# stm32_vcc.net
KiCad netlist of a schematic drawn in Altium Designer
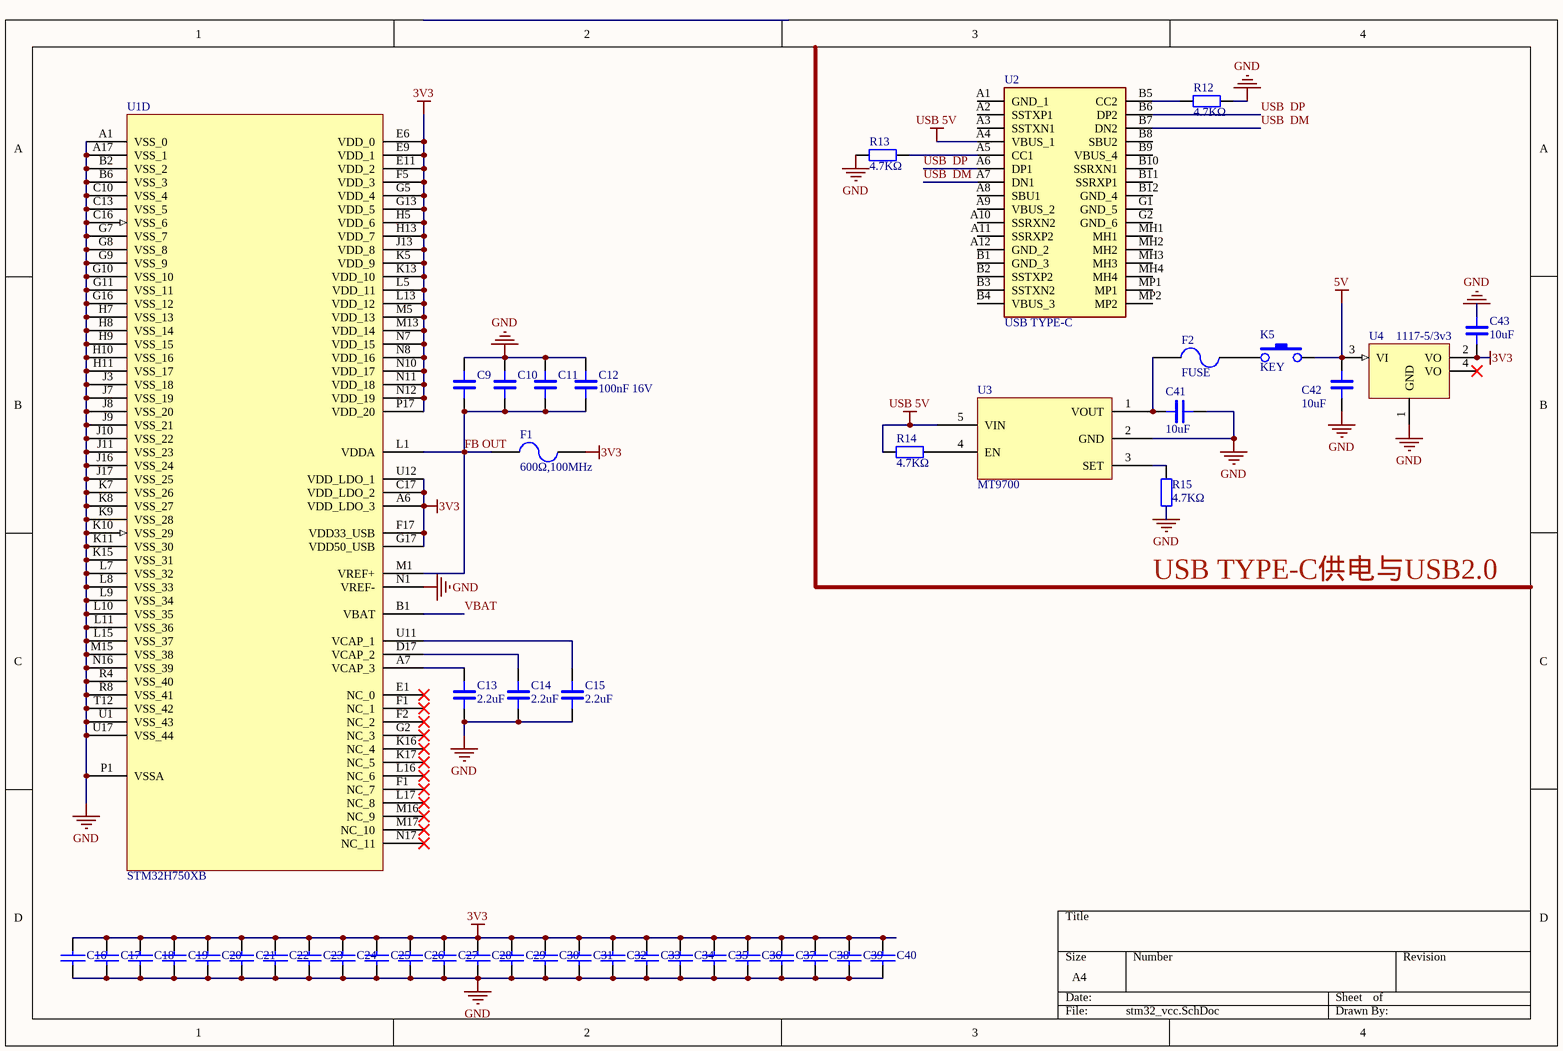
[diagram p0: stm32_vcc.SchDoc]

(export (version "E")
  (design (tool "Eeschema 10.0.6"))
  (components
    (comp (ref "C9")
      (value "100nF 16V")
      (footprint "0805")
      (description "Capacitor")
      (libsource (lib "General") (part "CAP"))
    )
    (comp (ref "C10")
      (value "100nF 16V")
      (footprint "0805")
      (description "Capacitor")
      (libsource (lib "General") (part "CAP"))
    )
    (comp (ref "C11")
      (value "100nF 16V")
      (footprint "0805")
      (description "Capacitor")
      (libsource (lib "General") (part "CAP"))
    )
    (comp (ref "C12")
      (value "100nF 16V")
      (footprint "0805")
      (description "Capacitor")
      (libsource (lib "General") (part "CAP"))
    )
    (comp (ref "C13")
      (value "2.2uF")
      (footprint "0805")
      (description "Capacitor")
      (libsource (lib "General") (part "CAP"))
    )
    (comp (ref "C14")
      (value "2.2uF")
      (footprint "0805")
      (description "Capacitor")
      (libsource (lib "General") (part "CAP"))
    )
    (comp (ref "C15")
      (value "2.2uF")
      (footprint "0805")
      (description "Capacitor")
      (libsource (lib "General") (part "CAP"))
    )
    (comp (ref "C16")
      (value "104 16V")
      (footprint "0805C")
      (description "无极性电容")
      (libsource (lib "电容") (part "CAP"))
    )
    (comp (ref "C17")
      (value "104 16V")
      (footprint "0805C")
      (description "无极性电容")
      (libsource (lib "电容") (part "CAP"))
    )
    (comp (ref "C18")
      (value "104 16V")
      (footprint "0805C")
      (description "无极性电容")
      (libsource (lib "电容") (part "CAP"))
    )
    (comp (ref "C19")
      (value "104 16V")
      (footprint "0805C")
      (description "无极性电容")
      (libsource (lib "电容") (part "CAP"))
    )
    (comp (ref "C20")
      (value "104 16V")
      (footprint "0805C")
      (description "无极性电容")
      (libsource (lib "电容") (part "CAP"))
    )
    (comp (ref "C21")
      (value "104 16V")
      (footprint "0805C")
      (description "无极性电容")
      (libsource (lib "电容") (part "CAP"))
    )
    (comp (ref "C22")
      (value "104 16V")
      (footprint "0805C")
      (description "无极性电容")
      (libsource (lib "电容") (part "CAP"))
    )
    (comp (ref "C23")
      (value "104 16V")
      (footprint "0805C")
      (description "无极性电容")
      (libsource (lib "电容") (part "CAP"))
    )
    (comp (ref "C24")
      (value "104 16V")
      (footprint "0805C")
      (description "无极性电容")
      (libsource (lib "电容") (part "CAP"))
    )
    (comp (ref "C25")
      (value "104 16V")
      (footprint "0805C")
      (description "无极性电容")
      (libsource (lib "电容") (part "CAP"))
    )
    (comp (ref "C26")
      (value "104 16V")
      (footprint "0805C")
      (description "无极性电容")
      (libsource (lib "电容") (part "CAP"))
    )
    (comp (ref "C27")
      (value "104 16V")
      (footprint "0805C")
      (description "无极性电容")
      (libsource (lib "电容") (part "CAP"))
    )
    (comp (ref "C28")
      (value "104 16V")
      (footprint "0805C")
      (description "无极性电容")
      (libsource (lib "电容") (part "CAP"))
    )
    (comp (ref "C29")
      (value "104 16V")
      (footprint "0805C")
      (description "无极性电容")
      (libsource (lib "电容") (part "CAP"))
    )
    (comp (ref "C30")
      (value "104 16V")
      (footprint "0805C")
      (description "无极性电容")
      (libsource (lib "电容") (part "CAP"))
    )
    (comp (ref "C31")
      (value "104 16V")
      (footprint "0805C")
      (description "无极性电容")
      (libsource (lib "电容") (part "CAP"))
    )
    (comp (ref "C32")
      (value "104 16V")
      (footprint "0805C")
      (description "无极性电容")
      (libsource (lib "电容") (part "CAP"))
    )
    (comp (ref "C33")
      (value "104 16V")
      (footprint "0805C")
      (description "无极性电容")
      (libsource (lib "电容") (part "CAP"))
    )
    (comp (ref "C34")
      (value "104 16V")
      (footprint "0805C")
      (description "无极性电容")
      (libsource (lib "电容") (part "CAP"))
    )
    (comp (ref "C35")
      (value "104 16V")
      (footprint "0805C")
      (description "无极性电容")
      (libsource (lib "电容") (part "CAP"))
    )
    (comp (ref "C36")
      (value "104 16V")
      (footprint "0805C")
      (description "无极性电容")
      (libsource (lib "电容") (part "CAP"))
    )
    (comp (ref "C37")
      (value "104 16V")
      (footprint "0805C")
      (description "无极性电容")
      (libsource (lib "电容") (part "CAP"))
    )
    (comp (ref "C38")
      (value "104 16V")
      (footprint "0805C")
      (description "无极性电容")
      (libsource (lib "电容") (part "CAP"))
    )
    (comp (ref "C39")
      (value "104 16V")
      (footprint "0805C")
      (description "无极性电容")
      (libsource (lib "电容") (part "CAP"))
    )
    (comp (ref "C40")
      (value "104 16V")
      (footprint "0805C")
      (description "无极性电容")
      (libsource (lib "电容") (part "CAP"))
    )
    (comp (ref "C41")
      (value "10uF")
      (footprint "0805")
      (description "Capacitor")
      (libsource (lib "General") (part "CAP"))
    )
    (comp (ref "C42")
      (value "10uF")
      (footprint "0805")
      (description "Capacitor")
      (libsource (lib "General") (part "CAP"))
    )
    (comp (ref "C43")
      (value "10uF")
      (footprint "CAP-0805")
      (description "Capacitor")
      (libsource (lib "General") (part "CAP"))
    )
    (comp (ref "F1") (value "600Ω,100MHz") (footprint "FUSE-1210") (libsource (lib "保险丝") (part "FUSE")))
    (comp (ref "F2")
      (value "FUSE")
      (footprint "FUSE-1210")
      (description "1000mA")
      (libsource (lib "保险丝") (part "FUSE"))
    )
    (comp (ref "K5") (value "KEY") (footprint "DIP-3X6X4.3") (libsource (lib "轻触开关") (part "KEY")))
    (comp (ref "R12")
      (value "4.7KΩ")
      (footprint "0805")
      (description "Resistor")
      (libsource (lib "General") (part "RES"))
    )
    (comp (ref "R13")
      (value "4.7KΩ")
      (footprint "0805")
      (description "Resistor")
      (libsource (lib "General") (part "RES"))
    )
    (comp (ref "R14")
      (value "4.7KΩ")
      (footprint "0805")
      (description "Resistor")
      (libsource (lib "General") (part "RES"))
    )
    (comp (ref "R15")
      (value "4.7KΩ")
      (footprint "0805")
      (description "Resistor")
      (libsource (lib "") (part "RES_1"))
    )
    (comp (ref "U1")
      (value "STM32H750XB")
      (footprint "BGA265C80P17X17_1400X1400X110")
      (libsource (lib "MainBoard") (part "STM32H750XB"))
    )
    (comp (ref "U2")
      (value "USB TYPE-C")
      (footprint "SamacSys:632723100011")
      (description "Integrated Circuit")
      (fields
        (field (name "MANUFACTURER_PART_NUMBER") "632723100011")
        (field (name "MOUSER PART NUMBER") "710-632723100011")
      )
      (libsource (lib "*") (part "632723100011"))
    )
    (comp (ref "U3") (value "MT9700") (footprint "SOT-23-5") (libsource (lib "MainBoard") (part "MT9700")))
    (comp (ref "U4")
      (value "1117-5/3v3")
      (footprint "SOT-23")
      (description "Linear Regulator")
      (libsource (lib "General") (part "1117"))
    )
  )
  (nets
    (net (code "1") (name "/FB OUT") (class "Default")
      (node (ref "C10") (pin "1") (pinfunction "1_1") (pintype "passive"))
      (node (ref "C11") (pin "1") (pinfunction "1_1") (pintype "passive"))
      (node (ref "C12") (pin "1") (pinfunction "1_1") (pintype "passive"))
      (node (ref "C9") (pin "1") (pinfunction "1_1") (pintype "passive"))
      (node (ref "F1") (pin "1") (pinfunction "1_1") (pintype "passive"))
      (node (ref "U1") (pin "L1") (pinfunction "VDDA_L1") (pintype "passive"))
      (node (ref "U1") (pin "M1") (pinfunction "VREF+_M1") (pintype "passive"))
    )
    (net (code "2") (name "/USB  DM") (class "Default")
      (node (ref "U2") (pin "A7") (pinfunction "DN1_A7") (pintype "passive"))
      (node (ref "U2") (pin "B7") (pinfunction "DN2_B7") (pintype "passive"))
    )
    (net (code "3") (name "/USB  DP") (class "Default")
      (node (ref "U2") (pin "A6") (pinfunction "DP1_A6") (pintype "passive"))
      (node (ref "U2") (pin "B6") (pinfunction "DP2_B6") (pintype "passive"))
    )
    (net (code "4") (name "/VBAT") (class "Default")
      (node (ref "U1") (pin "B1") (pinfunction "VBAT_B1") (pintype "passive"))
    )
    (net (code "5") (name "3V3") (class "Default")
      (node (ref "C16") (pin "2") (pinfunction "2_2") (pintype "passive"))
      (node (ref "C17") (pin "2") (pinfunction "2_2") (pintype "passive"))
      (node (ref "C18") (pin "2") (pinfunction "2_2") (pintype "passive"))
      (node (ref "C19") (pin "2") (pinfunction "2_2") (pintype "passive"))
      (node (ref "C20") (pin "2") (pinfunction "2_2") (pintype "passive"))
      (node (ref "C21") (pin "2") (pinfunction "2_2") (pintype "passive"))
      (node (ref "C22") (pin "2") (pinfunction "2_2") (pintype "passive"))
      (node (ref "C23") (pin "2") (pinfunction "2_2") (pintype "passive"))
      (node (ref "C24") (pin "2") (pinfunction "2_2") (pintype "passive"))
      (node (ref "C25") (pin "2") (pinfunction "2_2") (pintype "passive"))
      (node (ref "C26") (pin "2") (pinfunction "2_2") (pintype "passive"))
      (node (ref "C27") (pin "2") (pinfunction "2_2") (pintype "passive"))
      (node (ref "C28") (pin "2") (pinfunction "2_2") (pintype "passive"))
      (node (ref "C29") (pin "2") (pinfunction "2_2") (pintype "passive"))
      (node (ref "C30") (pin "2") (pinfunction "2_2") (pintype "passive"))
      (node (ref "C31") (pin "2") (pinfunction "2_2") (pintype "passive"))
      (node (ref "C32") (pin "2") (pinfunction "2_2") (pintype "passive"))
      (node (ref "C33") (pin "2") (pinfunction "2_2") (pintype "passive"))
      (node (ref "C34") (pin "2") (pinfunction "2_2") (pintype "passive"))
      (node (ref "C35") (pin "2") (pinfunction "2_2") (pintype "passive"))
      (node (ref "C36") (pin "2") (pinfunction "2_2") (pintype "passive"))
      (node (ref "C37") (pin "2") (pinfunction "2_2") (pintype "passive"))
      (node (ref "C38") (pin "2") (pinfunction "2_2") (pintype "passive"))
      (node (ref "C39") (pin "2") (pinfunction "2_2") (pintype "passive"))
      (node (ref "C40") (pin "2") (pinfunction "2_2") (pintype "passive"))
      (node (ref "C43") (pin "2") (pinfunction "2_2") (pintype "passive"))
      (node (ref "F1") (pin "2") (pinfunction "2_2") (pintype "passive"))
      (node (ref "U1") (pin "A6") (pinfunction "VDD_LDO_3_A6") (pintype "passive"))
      (node (ref "U1") (pin "C17") (pinfunction "VDD_LDO_2_C17") (pintype "passive"))
      (node (ref "U1") (pin "E11") (pinfunction "VDD_2_E11") (pintype "passive"))
      (node (ref "U1") (pin "E6") (pinfunction "VDD_0_E6") (pintype "passive"))
      (node (ref "U1") (pin "E9") (pinfunction "VDD_1_E9") (pintype "passive"))
      (node (ref "U1") (pin "F17") (pinfunction "VDD33_USB_F17") (pintype "passive"))
      (node (ref "U1") (pin "F5") (pinfunction "VDD_3_F5") (pintype "passive"))
      (node (ref "U1") (pin "G13") (pinfunction "VDD_5_G13") (pintype "passive"))
      (node (ref "U1") (pin "G17") (pinfunction "VDD50_USB_G17") (pintype "passive"))
      (node (ref "U1") (pin "G5") (pinfunction "VDD_4_G5") (pintype "passive"))
      (node (ref "U1") (pin "H13") (pinfunction "VDD_7_H13") (pintype "passive"))
      (node (ref "U1") (pin "H5") (pinfunction "VDD_6_H5") (pintype "passive"))
      (node (ref "U1") (pin "J13") (pinfunction "VDD_8_J13") (pintype "passive"))
      (node (ref "U1") (pin "K13") (pinfunction "VDD_10_K13") (pintype "passive"))
      (node (ref "U1") (pin "K5") (pinfunction "VDD_9_K5") (pintype "passive"))
      (node (ref "U1") (pin "L13") (pinfunction "VDD_12_L13") (pintype "passive"))
      (node (ref "U1") (pin "L5") (pinfunction "VDD_11_L5") (pintype "passive"))
      (node (ref "U1") (pin "M13") (pinfunction "VDD_14_M13") (pintype "passive"))
      (node (ref "U1") (pin "M5") (pinfunction "VDD_13_M5") (pintype "passive"))
      (node (ref "U1") (pin "N10") (pinfunction "VDD_17_N10") (pintype "passive"))
      (node (ref "U1") (pin "N11") (pinfunction "VDD_18_N11") (pintype "passive"))
      (node (ref "U1") (pin "N12") (pinfunction "VDD_19_N12") (pintype "passive"))
      (node (ref "U1") (pin "N7") (pinfunction "VDD_15_N7") (pintype "passive"))
      (node (ref "U1") (pin "N8") (pinfunction "VDD_16_N8") (pintype "passive"))
      (node (ref "U1") (pin "P17") (pinfunction "VDD_20_P17") (pintype "passive"))
      (node (ref "U1") (pin "U12") (pinfunction "VDD_LDO_1_U12") (pintype "passive"))
      (node (ref "U4") (pin "2") (pinfunction "VO_2") (pintype "power_in"))
    )
    (net (code "6") (name "5V") (class "Default")
      (node (ref "C42") (pin "1") (pinfunction "1_1") (pintype "passive"))
      (node (ref "K5") (pin "3") (pinfunction "3_3") (pintype "passive"))
      (node (ref "U4") (pin "3") (pinfunction "VI_3") (pintype "input"))
    )
    (net (code "7") (name "GND") (class "Default")
      (node (ref "C10") (pin "2") (pinfunction "2_2") (pintype "passive"))
      (node (ref "C11") (pin "2") (pinfunction "2_2") (pintype "passive"))
      (node (ref "C12") (pin "2") (pinfunction "2_2") (pintype "passive"))
      (node (ref "C13") (pin "1") (pinfunction "1_1") (pintype "passive"))
      (node (ref "C14") (pin "1") (pinfunction "1_1") (pintype "passive"))
      (node (ref "C15") (pin "1") (pinfunction "1_1") (pintype "passive"))
      (node (ref "C16") (pin "1") (pinfunction "1_1") (pintype "passive"))
      (node (ref "C17") (pin "1") (pinfunction "1_1") (pintype "passive"))
      (node (ref "C18") (pin "1") (pinfunction "1_1") (pintype "passive"))
      (node (ref "C19") (pin "1") (pinfunction "1_1") (pintype "passive"))
      (node (ref "C20") (pin "1") (pinfunction "1_1") (pintype "passive"))
      (node (ref "C21") (pin "1") (pinfunction "1_1") (pintype "passive"))
      (node (ref "C22") (pin "1") (pinfunction "1_1") (pintype "passive"))
      (node (ref "C23") (pin "1") (pinfunction "1_1") (pintype "passive"))
      (node (ref "C24") (pin "1") (pinfunction "1_1") (pintype "passive"))
      (node (ref "C25") (pin "1") (pinfunction "1_1") (pintype "passive"))
      (node (ref "C26") (pin "1") (pinfunction "1_1") (pintype "passive"))
      (node (ref "C27") (pin "1") (pinfunction "1_1") (pintype "passive"))
      (node (ref "C28") (pin "1") (pinfunction "1_1") (pintype "passive"))
      (node (ref "C29") (pin "1") (pinfunction "1_1") (pintype "passive"))
      (node (ref "C30") (pin "1") (pinfunction "1_1") (pintype "passive"))
      (node (ref "C31") (pin "1") (pinfunction "1_1") (pintype "passive"))
      (node (ref "C32") (pin "1") (pinfunction "1_1") (pintype "passive"))
      (node (ref "C33") (pin "1") (pinfunction "1_1") (pintype "passive"))
      (node (ref "C34") (pin "1") (pinfunction "1_1") (pintype "passive"))
      (node (ref "C35") (pin "1") (pinfunction "1_1") (pintype "passive"))
      (node (ref "C36") (pin "1") (pinfunction "1_1") (pintype "passive"))
      (node (ref "C37") (pin "1") (pinfunction "1_1") (pintype "passive"))
      (node (ref "C38") (pin "1") (pinfunction "1_1") (pintype "passive"))
      (node (ref "C39") (pin "1") (pinfunction "1_1") (pintype "passive"))
      (node (ref "C40") (pin "1") (pinfunction "1_1") (pintype "passive"))
      (node (ref "C41") (pin "1") (pinfunction "1_1") (pintype "passive"))
      (node (ref "C42") (pin "2") (pinfunction "2_2") (pintype "passive"))
      (node (ref "C43") (pin "1") (pinfunction "1_1") (pintype "passive"))
      (node (ref "C9") (pin "2") (pinfunction "2_2") (pintype "passive"))
      (node (ref "R12") (pin "1") (pinfunction "1_1") (pintype "passive"))
      (node (ref "R13") (pin "2") (pinfunction "2_2") (pintype "passive"))
      (node (ref "R15") (pin "2") (pinfunction "2_2") (pintype "passive"))
      (node (ref "U1") (pin "A1") (pinfunction "VSS_0_A1") (pintype "passive"))
      (node (ref "U1") (pin "A17") (pinfunction "VSS_1_A17") (pintype "passive"))
      (node (ref "U1") (pin "B2") (pinfunction "VSS_2_B2") (pintype "passive"))
      (node (ref "U1") (pin "B6") (pinfunction "VSS_3_B6") (pintype "passive"))
      (node (ref "U1") (pin "C10") (pinfunction "VSS_4_C10") (pintype "passive"))
      (node (ref "U1") (pin "C13") (pinfunction "VSS_5_C13") (pintype "passive"))
      (node (ref "U1") (pin "C16") (pinfunction "VSS_6_C16") (pintype "input"))
      (node (ref "U1") (pin "G10") (pinfunction "VSS_10_G10") (pintype "passive"))
      (node (ref "U1") (pin "G11") (pinfunction "VSS_11_G11") (pintype "passive"))
      (node (ref "U1") (pin "G16") (pinfunction "VSS_12_G16") (pintype "passive"))
      (node (ref "U1") (pin "G7") (pinfunction "VSS_7_G7") (pintype "passive"))
      (node (ref "U1") (pin "G8") (pinfunction "VSS_8_G8") (pintype "passive"))
      (node (ref "U1") (pin "G9") (pinfunction "VSS_9_G9") (pintype "passive"))
      (node (ref "U1") (pin "H10") (pinfunction "VSS_16_H10") (pintype "passive"))
      (node (ref "U1") (pin "H11") (pinfunction "VSS_17_H11") (pintype "passive"))
      (node (ref "U1") (pin "H7") (pinfunction "VSS_13_H7") (pintype "passive"))
      (node (ref "U1") (pin "H8") (pinfunction "VSS_14_H8") (pintype "passive"))
      (node (ref "U1") (pin "H9") (pinfunction "VSS_15_H9") (pintype "passive"))
      (node (ref "U1") (pin "J10") (pinfunction "VSS_22_J10") (pintype "passive"))
      (node (ref "U1") (pin "J11") (pinfunction "VSS_23_J11") (pintype "passive"))
      (node (ref "U1") (pin "J16") (pinfunction "VSS_24_J16") (pintype "power_in"))
      (node (ref "U1") (pin "J17") (pinfunction "VSS_25_J17") (pintype "passive"))
      (node (ref "U1") (pin "J3") (pinfunction "VSS_18_J3") (pintype "passive"))
      (node (ref "U1") (pin "J7") (pinfunction "VSS_19_J7") (pintype "passive"))
      (node (ref "U1") (pin "J8") (pinfunction "VSS_20_J8") (pintype "passive"))
      (node (ref "U1") (pin "J9") (pinfunction "VSS_21_J9") (pintype "passive"))
      (node (ref "U1") (pin "K10") (pinfunction "VSS_29_K10") (pintype "input"))
      (node (ref "U1") (pin "K11") (pinfunction "VSS_30_K11") (pintype "passive"))
      (node (ref "U1") (pin "K15") (pinfunction "VSS_31_K15") (pintype "passive"))
      (node (ref "U1") (pin "K7") (pinfunction "VSS_26_K7") (pintype "passive"))
      (node (ref "U1") (pin "K8") (pinfunction "VSS_27_K8") (pintype "passive"))
      (node (ref "U1") (pin "K9") (pinfunction "VSS_28_K9") (pintype "passive"))
      (node (ref "U1") (pin "L10") (pinfunction "VSS_35_L10") (pintype "passive"))
      (node (ref "U1") (pin "L11") (pinfunction "VSS_36_L11") (pintype "passive"))
      (node (ref "U1") (pin "L15") (pinfunction "VSS_37_L15") (pintype "passive"))
      (node (ref "U1") (pin "L7") (pinfunction "VSS_32_L7") (pintype "passive"))
      (node (ref "U1") (pin "L8") (pinfunction "VSS_33_L8") (pintype "passive"))
      (node (ref "U1") (pin "L9") (pinfunction "VSS_34_L9") (pintype "passive"))
      (node (ref "U1") (pin "M15") (pinfunction "VSS_38_M15") (pintype "passive"))
      (node (ref "U1") (pin "N1") (pinfunction "VREF-_N1") (pintype "passive"))
      (node (ref "U1") (pin "N16") (pinfunction "VSS_39_N16") (pintype "passive"))
      (node (ref "U1") (pin "P1") (pinfunction "VSSA_P1") (pintype "passive"))
      (node (ref "U1") (pin "R4") (pinfunction "VSS_40_R4") (pintype "passive"))
      (node (ref "U1") (pin "R8") (pinfunction "VSS_41_R8") (pintype "passive"))
      (node (ref "U1") (pin "T12") (pinfunction "VSS_42_T12") (pintype "passive"))
      (node (ref "U1") (pin "U1") (pinfunction "VSS_43_U1") (pintype "passive"))
      (node (ref "U1") (pin "U17") (pinfunction "VSS_44_U17") (pintype "passive"))
      (node (ref "U3") (pin "2") (pinfunction "GND_2") (pintype "passive"))
      (node (ref "U4") (pin "1") (pinfunction "GND_1") (pintype "power_in"))
    )
    (net (code "8") (name "Net-(F2-Pad2)") (class "Default")
      (node (ref "F2") (pin "2") (pinfunction "2_2") (pintype "passive"))
      (node (ref "K5") (pin "1") (pinfunction "1_1") (pintype "passive"))
    )
    (net (code "9") (name "Net-(U1D-VCAP_1)") (class "Default")
      (node (ref "C15") (pin "2") (pinfunction "2_2") (pintype "passive"))
      (node (ref "U1") (pin "U11") (pinfunction "VCAP_1_U11") (pintype "passive"))
    )
    (net (code "10") (name "Net-(U1D-VCAP_2)") (class "Default")
      (node (ref "C14") (pin "2") (pinfunction "2_2") (pintype "passive"))
      (node (ref "U1") (pin "D17") (pinfunction "VCAP_2_D17") (pintype "passive"))
    )
    (net (code "11") (name "Net-(U1D-VCAP_3)") (class "Default")
      (node (ref "C13") (pin "2") (pinfunction "2_2") (pintype "passive"))
      (node (ref "U1") (pin "A7") (pinfunction "VCAP_3_A7") (pintype "passive"))
    )
    (net (code "12") (name "Net-(U2-CC1)") (class "Default")
      (node (ref "R13") (pin "1") (pinfunction "1_1") (pintype "passive"))
      (node (ref "U2") (pin "A5") (pinfunction "CC1_A5") (pintype "passive"))
    )
    (net (code "13") (name "Net-(U2-CC2)") (class "Default")
      (node (ref "R12") (pin "2") (pinfunction "2_2") (pintype "passive"))
      (node (ref "U2") (pin "B5") (pinfunction "CC2_B5") (pintype "passive"))
    )
    (net (code "14") (name "Net-(U3-EN)") (class "Default")
      (node (ref "R14") (pin "1") (pinfunction "1_1") (pintype "passive"))
      (node (ref "U3") (pin "4") (pinfunction "EN_4") (pintype "passive"))
    )
    (net (code "15") (name "Net-(U3-SET)") (class "Default")
      (node (ref "R15") (pin "1") (pinfunction "1_1") (pintype "passive"))
      (node (ref "U3") (pin "3") (pinfunction "SET_3") (pintype "passive"))
    )
    (net (code "16") (name "Net-(U3-VOUT)") (class "Default")
      (node (ref "C41") (pin "2") (pinfunction "2_2") (pintype "passive"))
      (node (ref "F2") (pin "1") (pinfunction "1_1") (pintype "passive"))
      (node (ref "U3") (pin "1") (pinfunction "VOUT_1") (pintype "passive"))
    )
    (net (code "17") (name "USB 5V") (class "Default")
      (node (ref "R14") (pin "2") (pinfunction "2_2") (pintype "passive"))
      (node (ref "U2") (pin "A4") (pinfunction "VBUS_1_A4") (pintype "passive"))
      (node (ref "U3") (pin "5") (pinfunction "VIN_5") (pintype "passive"))
    )
    (net (code "18") (name "unconnected-(U1D-NC_0-PadE1)") (class "Default")
      (node (ref "U1") (pin "E1") (pinfunction "NC_0_E1") (pintype "passive+no_connect"))
    )
    (net (code "19") (name "unconnected-(U1D-NC_1-PadF1)") (class "Default")
      (node (ref "U1") (pin "F1") (pinfunction "NC_1_F1") (pintype "passive+no_connect"))
    )
    (net (code "20") (name "unconnected-(U1D-NC_2-PadF2)") (class "Default")
      (node (ref "U1") (pin "F2") (pinfunction "NC_2_F2") (pintype "passive+no_connect"))
    )
    (net (code "21") (name "unconnected-(U1D-NC_3-PadG2)") (class "Default")
      (node (ref "U1") (pin "G2") (pinfunction "NC_3_G2") (pintype "passive+no_connect"))
    )
    (net (code "22") (name "unconnected-(U1D-NC_4-PadK16)") (class "Default")
      (node (ref "U1") (pin "K16") (pinfunction "NC_4_K16") (pintype "passive+no_connect"))
    )
    (net (code "23") (name "unconnected-(U1D-NC_5-PadK17)") (class "Default")
      (node (ref "U1") (pin "K17") (pinfunction "NC_5_K17") (pintype "passive+no_connect"))
    )
    (net (code "24") (name "unconnected-(U1D-NC_6-PadL16)") (class "Default")
      (node (ref "U1") (pin "L16") (pinfunction "NC_6_L16") (pintype "passive+no_connect"))
    )
    (net (code "25") (name "unconnected-(U1D-NC_7-PadF1)") (class "Default")
      (node (ref "U1") (pin "F1") (pinfunction "NC_7_F1") (pintype "passive+no_connect"))
    )
    (net (code "26") (name "unconnected-(U1D-NC_8-PadL17)") (class "Default")
      (node (ref "U1") (pin "L17") (pinfunction "NC_8_L17") (pintype "passive+no_connect"))
    )
    (net (code "27") (name "unconnected-(U1D-NC_9-PadM16)") (class "Default")
      (node (ref "U1") (pin "M16") (pinfunction "NC_9_M16") (pintype "passive+no_connect"))
    )
    (net (code "28") (name "unconnected-(U1D-NC_10-PadM17)") (class "Default")
      (node (ref "U1") (pin "M17") (pinfunction "NC_10_M17") (pintype "passive+no_connect"))
    )
    (net (code "29") (name "unconnected-(U1D-NC_11-PadN17)") (class "Default")
      (node (ref "U1") (pin "N17") (pinfunction "NC_11_N17") (pintype "passive+no_connect"))
    )
    (net (code "30") (name "unconnected-(U2-GND_1-PadA1)") (class "Default")
      (node (ref "U2") (pin "A1") (pinfunction "GND_1_A1") (pintype "passive"))
    )
    (net (code "31") (name "unconnected-(U2-GND_2-PadA12)") (class "Default")
      (node (ref "U2") (pin "A12") (pinfunction "GND_2_A12") (pintype "passive"))
    )
    (net (code "32") (name "unconnected-(U2-GND_3-PadB1)") (class "Default")
      (node (ref "U2") (pin "B1") (pinfunction "GND_3_B1") (pintype "passive"))
    )
    (net (code "33") (name "unconnected-(U2-GND_4-PadB12)") (class "Default")
      (node (ref "U2") (pin "B12") (pinfunction "GND_4_B12") (pintype "passive"))
    )
    (net (code "34") (name "unconnected-(U2-GND_5-PadG1)") (class "Default")
      (node (ref "U2") (pin "G1") (pinfunction "GND_5_G1") (pintype "passive"))
    )
    (net (code "35") (name "unconnected-(U2-GND_6-PadG2)") (class "Default")
      (node (ref "U2") (pin "G2") (pinfunction "GND_6_G2") (pintype "passive"))
    )
    (net (code "36") (name "unconnected-(U2-PadMH1)") (class "Default")
      (node (ref "U2") (pin "MH1") (pinfunction "MH1_MH1") (pintype "passive"))
    )
    (net (code "37") (name "unconnected-(U2-PadMH2)") (class "Default")
      (node (ref "U2") (pin "MH2") (pinfunction "MH2_MH2") (pintype "passive"))
    )
    (net (code "38") (name "unconnected-(U2-PadMH3)") (class "Default")
      (node (ref "U2") (pin "MH3") (pinfunction "MH3_MH3") (pintype "passive"))
    )
    (net (code "39") (name "unconnected-(U2-PadMH4)") (class "Default")
      (node (ref "U2") (pin "MH4") (pinfunction "MH4_MH4") (pintype "passive"))
    )
    (net (code "40") (name "unconnected-(U2-PadMP1)") (class "Default")
      (node (ref "U2") (pin "MP1") (pinfunction "MP1_MP1") (pintype "passive"))
    )
    (net (code "41") (name "unconnected-(U2-PadMP2)") (class "Default")
      (node (ref "U2") (pin "MP2") (pinfunction "MP2_MP2") (pintype "passive"))
    )
    (net (code "42") (name "unconnected-(U2-SBU1-PadA8)") (class "Default")
      (node (ref "U2") (pin "A8") (pinfunction "SBU1_A8") (pintype "passive"))
    )
    (net (code "43") (name "unconnected-(U2-SBU2-PadB8)") (class "Default")
      (node (ref "U2") (pin "B8") (pinfunction "SBU2_B8") (pintype "passive"))
    )
    (net (code "44") (name "unconnected-(U2-SSRXN1-PadB10)") (class "Default")
      (node (ref "U2") (pin "B10") (pinfunction "SSRXN1_B10") (pintype "passive"))
    )
    (net (code "45") (name "unconnected-(U2-SSRXN2-PadA10)") (class "Default")
      (node (ref "U2") (pin "A10") (pinfunction "SSRXN2_A10") (pintype "passive"))
    )
    (net (code "46") (name "unconnected-(U2-SSRXP1-PadB11)") (class "Default")
      (node (ref "U2") (pin "B11") (pinfunction "SSRXP1_B11") (pintype "passive"))
    )
    (net (code "47") (name "unconnected-(U2-SSRXP2-PadA11)") (class "Default")
      (node (ref "U2") (pin "A11") (pinfunction "SSRXP2_A11") (pintype "passive"))
    )
    (net (code "48") (name "unconnected-(U2-SSTXN1-PadA3)") (class "Default")
      (node (ref "U2") (pin "A3") (pinfunction "SSTXN1_A3") (pintype "passive"))
    )
    (net (code "49") (name "unconnected-(U2-SSTXN2-PadB3)") (class "Default")
      (node (ref "U2") (pin "B3") (pinfunction "SSTXN2_B3") (pintype "passive"))
    )
    (net (code "50") (name "unconnected-(U2-SSTXP1-PadA2)") (class "Default")
      (node (ref "U2") (pin "A2") (pinfunction "SSTXP1_A2") (pintype "passive"))
    )
    (net (code "51") (name "unconnected-(U2-SSTXP2-PadB2)") (class "Default")
      (node (ref "U2") (pin "B2") (pinfunction "SSTXP2_B2") (pintype "passive"))
    )
    (net (code "52") (name "unconnected-(U2-VBUS_2-PadA9)") (class "Default")
      (node (ref "U2") (pin "A9") (pinfunction "VBUS_2_A9") (pintype "passive"))
    )
    (net (code "53") (name "unconnected-(U2-VBUS_3-PadB4)") (class "Default")
      (node (ref "U2") (pin "B4") (pinfunction "VBUS_3_B4") (pintype "passive"))
    )
    (net (code "54") (name "unconnected-(U2-VBUS_4-PadB9)") (class "Default")
      (node (ref "U2") (pin "B9") (pinfunction "VBUS_4_B9") (pintype "passive"))
    )
    (net (code "55") (name "unconnected-(U4-VO-Pad4)") (class "Default")
      (node (ref "U4") (pin "4") (pinfunction "VO_4") (pintype "power_in+no_connect"))
    )
  )
)
